# design.net
KiCad netlist of a schematic drawn in Altium Designer
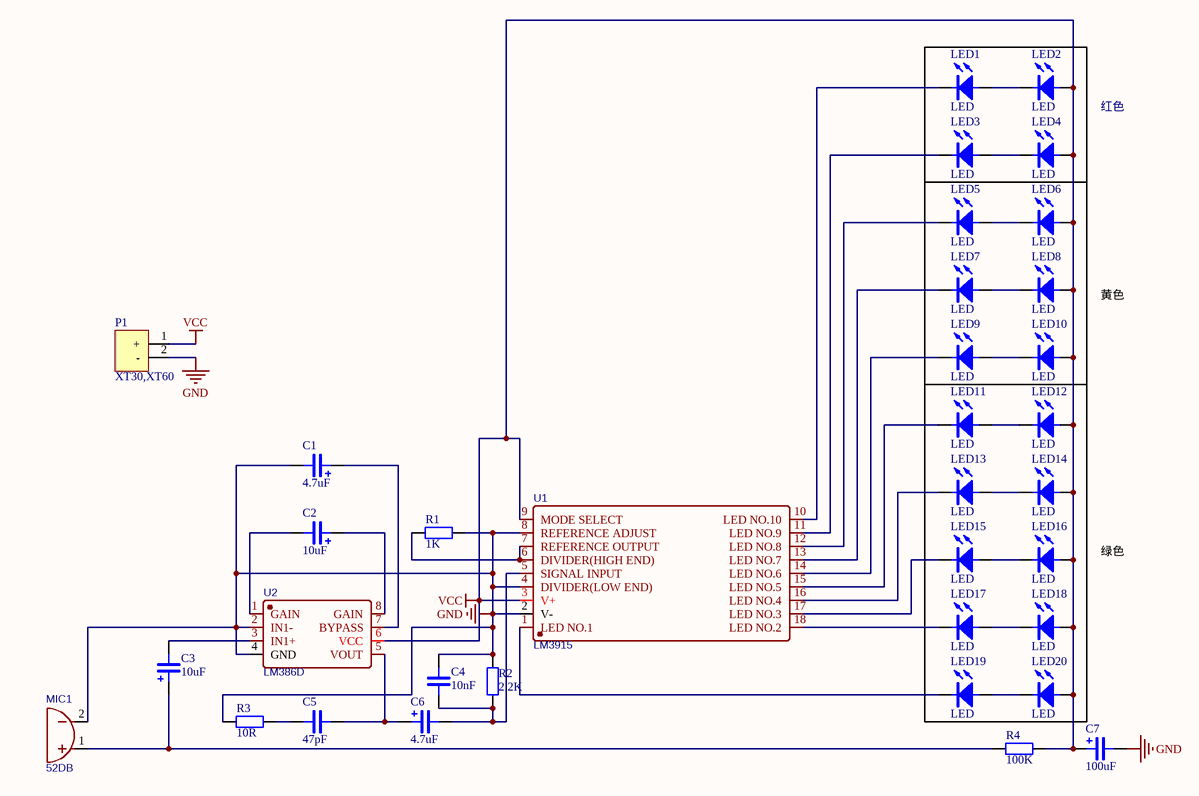
[diagram p0: 无线声量计.SchDoc]

(export (version "E")
  (design (tool "Eeschema 10.0.6"))
  (components
    (comp (ref "C1")
      (value "4.7uF")
      (footprint "CAP-6.3X6.3X12")
      (description "Tantalum Capacitor")
      (libsource (lib "General") (part "CAP-TANTALUM"))
    )
    (comp (ref "C2")
      (value "10uF")
      (footprint "CAP-6.3X6.3X12")
      (description "Tantalum Capacitor")
      (libsource (lib "General") (part "CAP-TANTALUM"))
    )
    (comp (ref "C3")
      (value "10uF")
      (footprint "CAP-6.3X6.3X12")
      (description "Tantalum Capacitor")
      (libsource (lib "General") (part "CAP-TANTALUM"))
    )
    (comp (ref "C4")
      (value "10nF")
      (footprint "0603_C")
      (description "Capacitor")
      (libsource (lib "General") (part "CAP"))
    )
    (comp (ref "C5")
      (value "47pF")
      (footprint "0603_C")
      (description "Capacitor")
      (libsource (lib "General") (part "CAP"))
    )
    (comp (ref "C6")
      (value "4.7uF")
      (footprint "CAP-6.3X6.3X12")
      (description "Tantalum Capacitor")
      (libsource (lib "General") (part "CAP-TANTALUM"))
    )
    (comp (ref "C7")
      (value "100uF")
      (footprint "CAP-6.3X6.3X12")
      (description "Tantalum Capacitor")
      (libsource (lib "General") (part "CAP-TANTALUM"))
    )
    (comp (ref "LED1")
      (value "LED")
      (footprint "LED 2.54mm 直插式 5mm")
      (libsource (lib "General") (part "LED"))
    )
    (comp (ref "LED2")
      (value "LED")
      (footprint "LED 2.54mm 直插式 5mm")
      (libsource (lib "General") (part "LED"))
    )
    (comp (ref "LED3")
      (value "LED")
      (footprint "LED 2.54mm 直插式 5mm")
      (libsource (lib "General") (part "LED"))
    )
    (comp (ref "LED4")
      (value "LED")
      (footprint "LED 2.54mm 直插式 5mm")
      (libsource (lib "General") (part "LED"))
    )
    (comp (ref "LED5")
      (value "LED")
      (footprint "LED 2.54mm 直插式 5mm")
      (libsource (lib "General") (part "LED"))
    )
    (comp (ref "LED6")
      (value "LED")
      (footprint "LED 2.54mm 直插式 5mm")
      (libsource (lib "General") (part "LED"))
    )
    (comp (ref "LED7")
      (value "LED")
      (footprint "LED 2.54mm 直插式 5mm")
      (libsource (lib "General") (part "LED"))
    )
    (comp (ref "LED8")
      (value "LED")
      (footprint "LED 2.54mm 直插式 5mm")
      (libsource (lib "General") (part "LED"))
    )
    (comp (ref "LED9")
      (value "LED")
      (footprint "LED 2.54mm 直插式 5mm")
      (libsource (lib "General") (part "LED"))
    )
    (comp (ref "LED10")
      (value "LED")
      (footprint "LED 2.54mm 直插式 5mm")
      (libsource (lib "General") (part "LED"))
    )
    (comp (ref "LED11")
      (value "LED")
      (footprint "LED 2.54mm 直插式 5mm")
      (libsource (lib "General") (part "LED"))
    )
    (comp (ref "LED12")
      (value "LED")
      (footprint "LED 2.54mm 直插式 5mm")
      (libsource (lib "General") (part "LED"))
    )
    (comp (ref "LED13")
      (value "LED")
      (footprint "LED 2.54mm 直插式 5mm")
      (libsource (lib "General") (part "LED"))
    )
    (comp (ref "LED14")
      (value "LED")
      (footprint "LED 2.54mm 直插式 5mm")
      (libsource (lib "General") (part "LED"))
    )
    (comp (ref "LED15")
      (value "LED")
      (footprint "LED 2.54mm 直插式 5mm")
      (libsource (lib "General") (part "LED"))
    )
    (comp (ref "LED16")
      (value "LED")
      (footprint "LED 2.54mm 直插式 5mm")
      (libsource (lib "General") (part "LED"))
    )
    (comp (ref "LED17")
      (value "LED")
      (footprint "LED 2.54mm 直插式 5mm")
      (libsource (lib "General") (part "LED"))
    )
    (comp (ref "LED18")
      (value "LED")
      (footprint "LED 2.54mm 直插式 5mm")
      (libsource (lib "General") (part "LED"))
    )
    (comp (ref "LED19")
      (value "LED")
      (footprint "LED 2.54mm 直插式 5mm")
      (libsource (lib "General") (part "LED"))
    )
    (comp (ref "LED20")
      (value "LED")
      (footprint "LED 2.54mm 直插式 5mm")
      (libsource (lib "General") (part "LED"))
    )
    (comp (ref "MIC1")
      (value "52DB")
      (footprint "MIC-TH_BD9.7-P2.54-D0.8-L-FD")
      (description "咪头")
      (fields
        (field (name "BOM_SUPPLIER PART") "C234012")
        (field (name "BOM_MANUFACTURER PART") "GMI9767P-30DB")
        (field (name "CONTRIBUTOR") "LCSC")
      )
      (libsource (lib "General") (part "52DB"))
    )
    (comp (ref "P1")
      (value "XT30,XT60")
      (footprint "XT60U-M")
      (description "电源接口")
      (libsource (lib "General") (part "XT"))
    )
    (comp (ref "R1")
      (value "1K")
      (footprint "0603_R")
      (description "Resistor")
      (libsource (lib "") (part "RES_1"))
    )
    (comp (ref "R2")
      (value "2.2K")
      (footprint "0603_R")
      (description "Resistor")
      (libsource (lib "") (part "RES_2"))
    )
    (comp (ref "R3")
      (value "10R")
      (footprint "0603_R")
      (description "Resistor")
      (libsource (lib "General") (part "RES"))
    )
    (comp (ref "R4")
      (value "100K")
      (footprint "0603_R")
      (description "Resistor")
      (libsource (lib "") (part "RES_1"))
    )
    (comp (ref "U1")
      (value "LM3915")
      (footprint "DIP-18")
      (description "LED照明驱动器")
      (fields
        (field (name "BOM_SUPPLIER PART") "C609778")
        (field (name "BOM_MANUFACTURER PART") "XD3915")
        (field (name "CONTRIBUTOR") "LCSC")
      )
      (libsource (lib "General") (part "LM3915"))
    )
    (comp (ref "U2")
      (value "LM386D")
      (footprint "DIP-8")
      (description "音频功率放大器")
      (fields (field (name "BOM_SUPPLIER PART") "C510560") (field (name "CONTRIBUTOR") "LCSC"))
      (libsource (lib "General") (part "LM386D"))
    )
  )
  (nets
    (net (code "1") (name "GND") (class "Default")
      (node (ref "C1") (pin "2") (pinfunction "2_2") (pintype "passive"))
      (node (ref "C4") (pin "2") (pinfunction "2_2") (pintype "passive"))
      (node (ref "C7") (pin "2") (pinfunction "2_2") (pintype "passive"))
      (node (ref "MIC1") (pin "2") (pinfunction "2_2") (pintype "passive"))
      (node (ref "P1") (pin "2") (pinfunction "-_2") (pintype "passive"))
      (node (ref "R1") (pin "1") (pinfunction "1_1") (pintype "passive"))
      (node (ref "R2") (pin "2") (pinfunction "2_2") (pintype "passive"))
      (node (ref "R3") (pin "1") (pinfunction "1_1") (pintype "passive"))
      (node (ref "U1") (pin "2") (pinfunction "V-_2") (pintype "passive"))
      (node (ref "U1") (pin "4") (pinfunction "DIVIDER(LOW_END)_4") (pintype "passive"))
      (node (ref "U1") (pin "8") (pinfunction "REFERENCE_ADJUST_8") (pintype "passive"))
      (node (ref "U2") (pin "2") (pinfunction "IN1-_2") (pintype "passive"))
      (node (ref "U2") (pin "4") (pinfunction "GND_4") (pintype "passive"))
    )
    (net (code "2") (name "Net-(C2-Pad1)") (class "Default")
      (node (ref "C2") (pin "1") (pinfunction "1_1") (pintype "passive"))
      (node (ref "U2") (pin "8") (pinfunction "GAIN_8") (pintype "passive"))
    )
    (net (code "3") (name "Net-(C2-Pad2)") (class "Default")
      (node (ref "C2") (pin "2") (pinfunction "2_2") (pintype "passive"))
      (node (ref "U2") (pin "1") (pinfunction "GAIN_1") (pintype "passive"))
    )
    (net (code "4") (name "Net-(C3-Pad1)") (class "Default")
      (node (ref "C3") (pin "1") (pinfunction "1_1") (pintype "passive"))
      (node (ref "MIC1") (pin "1") (pinfunction "1_1") (pintype "passive"))
      (node (ref "R4") (pin "2") (pinfunction "2_2") (pintype "passive"))
    )
    (net (code "5") (name "Net-(C5-Pad1)") (class "Default")
      (node (ref "C5") (pin "1") (pinfunction "1_1") (pintype "passive"))
      (node (ref "R3") (pin "2") (pinfunction "2_2") (pintype "passive"))
    )
    (net (code "6") (name "Net-(LED1-A)") (class "Default")
      (node (ref "LED1") (pin "1") (pinfunction "A_1") (pintype "passive"))
      (node (ref "LED2") (pin "2") (pinfunction "C_2") (pintype "passive"))
    )
    (net (code "7") (name "Net-(LED1-C)") (class "Default")
      (node (ref "LED1") (pin "2") (pinfunction "C_2") (pintype "passive"))
      (node (ref "U1") (pin "10") (pinfunction "LED_NO.10_10") (pintype "passive"))
    )
    (net (code "8") (name "Net-(LED3-A)") (class "Default")
      (node (ref "LED3") (pin "1") (pinfunction "A_1") (pintype "passive"))
      (node (ref "LED4") (pin "2") (pinfunction "C_2") (pintype "passive"))
    )
    (net (code "9") (name "Net-(LED3-C)") (class "Default")
      (node (ref "LED3") (pin "2") (pinfunction "C_2") (pintype "passive"))
      (node (ref "U1") (pin "11") (pinfunction "LED_NO.9_11") (pintype "passive"))
    )
    (net (code "10") (name "Net-(LED5-A)") (class "Default")
      (node (ref "LED5") (pin "1") (pinfunction "A_1") (pintype "passive"))
      (node (ref "LED6") (pin "2") (pinfunction "C_2") (pintype "passive"))
    )
    (net (code "11") (name "Net-(LED5-C)") (class "Default")
      (node (ref "LED5") (pin "2") (pinfunction "C_2") (pintype "passive"))
      (node (ref "U1") (pin "12") (pinfunction "LED_NO.8_12") (pintype "passive"))
    )
    (net (code "12") (name "Net-(LED7-A)") (class "Default")
      (node (ref "LED7") (pin "1") (pinfunction "A_1") (pintype "passive"))
      (node (ref "LED8") (pin "2") (pinfunction "C_2") (pintype "passive"))
    )
    (net (code "13") (name "Net-(LED7-C)") (class "Default")
      (node (ref "LED7") (pin "2") (pinfunction "C_2") (pintype "passive"))
      (node (ref "U1") (pin "13") (pinfunction "LED_NO.7_13") (pintype "passive"))
    )
    (net (code "14") (name "Net-(LED9-C)") (class "Default")
      (node (ref "LED9") (pin "2") (pinfunction "C_2") (pintype "passive"))
      (node (ref "U1") (pin "14") (pinfunction "LED_NO.6_14") (pintype "passive"))
    )
    (net (code "15") (name "Net-(LED10-C)") (class "Default")
      (node (ref "LED10") (pin "2") (pinfunction "C_2") (pintype "passive"))
      (node (ref "LED9") (pin "1") (pinfunction "A_1") (pintype "passive"))
    )
    (net (code "16") (name "Net-(LED11-A)") (class "Default")
      (node (ref "LED11") (pin "1") (pinfunction "A_1") (pintype "passive"))
      (node (ref "LED12") (pin "2") (pinfunction "C_2") (pintype "passive"))
    )
    (net (code "17") (name "Net-(LED11-C)") (class "Default")
      (node (ref "LED11") (pin "2") (pinfunction "C_2") (pintype "passive"))
      (node (ref "U1") (pin "15") (pinfunction "LED_NO.5_15") (pintype "passive"))
    )
    (net (code "18") (name "Net-(LED13-A)") (class "Default")
      (node (ref "LED13") (pin "1") (pinfunction "A_1") (pintype "passive"))
      (node (ref "LED14") (pin "2") (pinfunction "C_2") (pintype "passive"))
    )
    (net (code "19") (name "Net-(LED13-C)") (class "Default")
      (node (ref "LED13") (pin "2") (pinfunction "C_2") (pintype "passive"))
      (node (ref "U1") (pin "16") (pinfunction "LED_NO.4_16") (pintype "passive"))
    )
    (net (code "20") (name "Net-(LED15-A)") (class "Default")
      (node (ref "LED15") (pin "1") (pinfunction "A_1") (pintype "passive"))
      (node (ref "LED16") (pin "2") (pinfunction "C_2") (pintype "passive"))
    )
    (net (code "21") (name "Net-(LED15-C)") (class "Default")
      (node (ref "LED15") (pin "2") (pinfunction "C_2") (pintype "passive"))
      (node (ref "U1") (pin "17") (pinfunction "LED_NO.3_17") (pintype "passive"))
    )
    (net (code "22") (name "Net-(LED17-A)") (class "Default")
      (node (ref "LED17") (pin "1") (pinfunction "A_1") (pintype "passive"))
      (node (ref "LED18") (pin "2") (pinfunction "C_2") (pintype "passive"))
    )
    (net (code "23") (name "Net-(LED17-C)") (class "Default")
      (node (ref "LED17") (pin "2") (pinfunction "C_2") (pintype "passive"))
      (node (ref "U1") (pin "18") (pinfunction "LED_NO.2_18") (pintype "passive"))
    )
    (net (code "24") (name "Net-(LED19-A)") (class "Default")
      (node (ref "LED19") (pin "1") (pinfunction "A_1") (pintype "passive"))
      (node (ref "LED20") (pin "2") (pinfunction "C_2") (pintype "passive"))
    )
    (net (code "25") (name "Net-(LED19-C)") (class "Default")
      (node (ref "LED19") (pin "2") (pinfunction "C_2") (pintype "passive"))
      (node (ref "U1") (pin "1") (pinfunction "LED_NO.1_1") (pintype "passive"))
    )
    (net (code "26") (name "Net-(U1-DIVIDER(HIGH_END))") (class "Default")
      (node (ref "R1") (pin "2") (pinfunction "2_2") (pintype "passive"))
      (node (ref "U1") (pin "6") (pinfunction "DIVIDER(HIGH_END)_6") (pintype "passive"))
      (node (ref "U1") (pin "7") (pinfunction "REFERENCE_OUTPUT_7") (pintype "passive"))
    )
    (net (code "27") (name "Net-(U1-SIGNAL_INPUT)") (class "Default")
      (node (ref "C4") (pin "1") (pinfunction "1_1") (pintype "passive"))
      (node (ref "C6") (pin "2") (pinfunction "2_2") (pintype "passive"))
      (node (ref "R2") (pin "1") (pinfunction "1_1") (pintype "passive"))
      (node (ref "U1") (pin "5") (pinfunction "SIGNAL_INPUT_5") (pintype "passive"))
    )
    (net (code "28") (name "Net-(U2-BYPASS)") (class "Default")
      (node (ref "C1") (pin "1") (pinfunction "1_1") (pintype "passive"))
      (node (ref "U2") (pin "7") (pinfunction "BYPASS_7") (pintype "passive"))
    )
    (net (code "29") (name "Net-(U2-IN1+)") (class "Default")
      (node (ref "C3") (pin "2") (pinfunction "2_2") (pintype "passive"))
      (node (ref "U2") (pin "3") (pinfunction "IN1+_3") (pintype "passive"))
    )
    (net (code "30") (name "Net-(U2-VOUT)") (class "Default")
      (node (ref "C5") (pin "2") (pinfunction "2_2") (pintype "passive"))
      (node (ref "C6") (pin "1") (pinfunction "1_1") (pintype "passive"))
      (node (ref "U2") (pin "5") (pinfunction "VOUT_5") (pintype "passive"))
    )
    (net (code "31") (name "VCC") (class "Default")
      (node (ref "C7") (pin "1") (pinfunction "1_1") (pintype "passive"))
      (node (ref "LED10") (pin "1") (pinfunction "A_1") (pintype "passive"))
      (node (ref "LED12") (pin "1") (pinfunction "A_1") (pintype "passive"))
      (node (ref "LED14") (pin "1") (pinfunction "A_1") (pintype "passive"))
      (node (ref "LED16") (pin "1") (pinfunction "A_1") (pintype "passive"))
      (node (ref "LED18") (pin "1") (pinfunction "A_1") (pintype "passive"))
      (node (ref "LED2") (pin "1") (pinfunction "A_1") (pintype "passive"))
      (node (ref "LED20") (pin "1") (pinfunction "A_1") (pintype "passive"))
      (node (ref "LED4") (pin "1") (pinfunction "A_1") (pintype "passive"))
      (node (ref "LED6") (pin "1") (pinfunction "A_1") (pintype "passive"))
      (node (ref "LED8") (pin "1") (pinfunction "A_1") (pintype "passive"))
      (node (ref "P1") (pin "1") (pinfunction "+_1") (pintype "passive"))
      (node (ref "R4") (pin "1") (pinfunction "1_1") (pintype "passive"))
      (node (ref "U1") (pin "3") (pinfunction "V+_3") (pintype "passive"))
      (node (ref "U1") (pin "9") (pinfunction "MODE_SELECT_9") (pintype "passive"))
      (node (ref "U2") (pin "6") (pinfunction "VCC_6") (pintype "passive"))
    )
  )
)
